# bt-snes-aa-ncp1402-attiny25-pogo.net
KiCad netlist of a schematic drawn in EAGLE
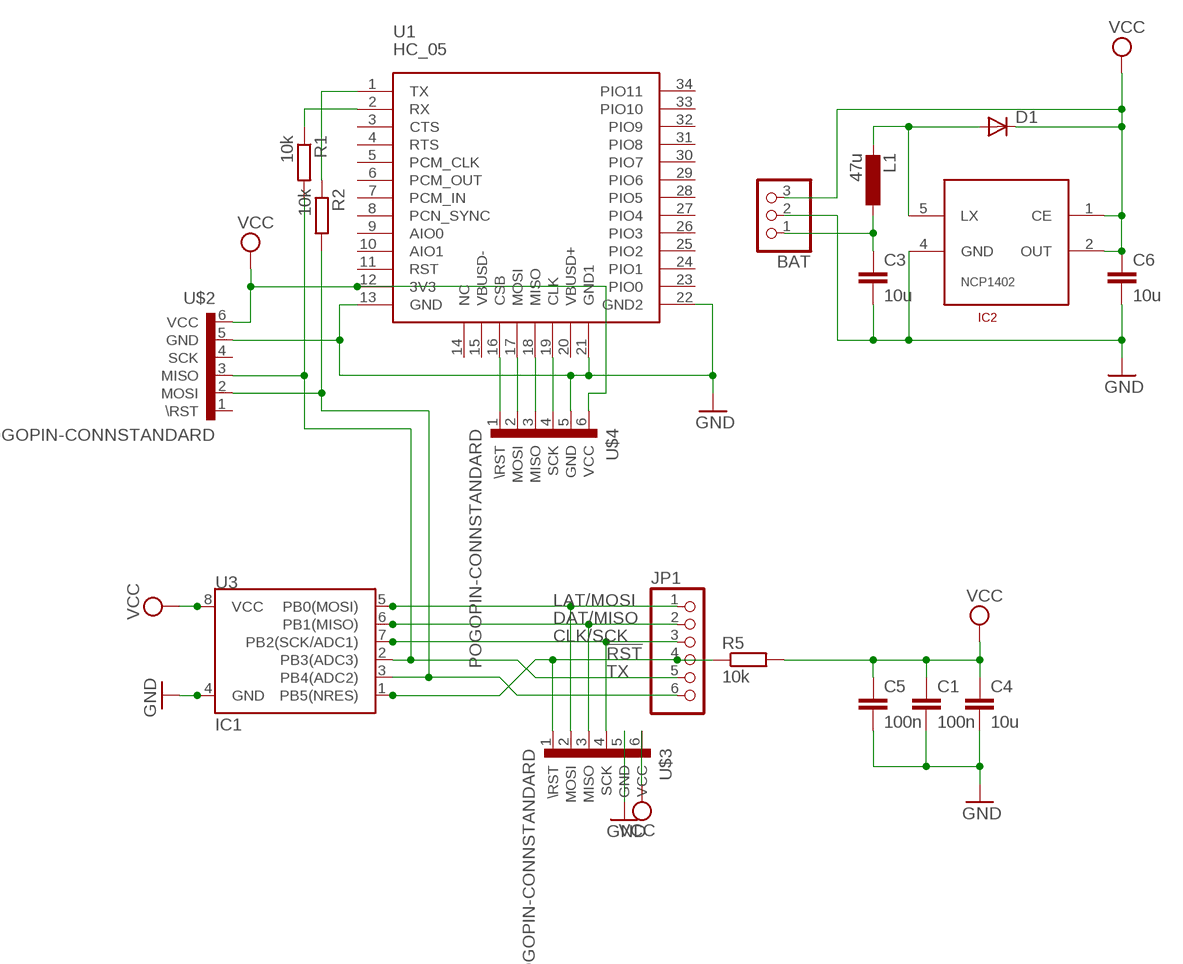
[diagram p0: schematic, sheet 1]

(export (version "E")
  (design (tool "Eeschema 10.0.6"))
  (components
    (comp (ref "BAT")
      (value "PINHD-1X3")
      (footprint "eagle-import:1X03")
      (libsource (lib "eagle-import") (part "PINHD-1X3"))
    )
    (comp (ref "C1")
      (value "100n")
      (footprint "eagle-import:C0805K")
      (libsource (lib "eagle-import") (part "C-EUC0805K"))
    )
    (comp (ref "C3")
      (value "10u")
      (footprint "eagle-import:C0805K")
      (libsource (lib "eagle-import") (part "C-EUC0805K"))
    )
    (comp (ref "C4")
      (value "10u")
      (footprint "eagle-import:C0805K")
      (libsource (lib "eagle-import") (part "C-EUC0805K"))
    )
    (comp (ref "C5")
      (value "100n")
      (footprint "eagle-import:C0805K")
      (libsource (lib "eagle-import") (part "C-EUC0805K"))
    )
    (comp (ref "C6")
      (value "10u")
      (footprint "eagle-import:C0805K")
      (libsource (lib "eagle-import") (part "C-EUC0805K"))
    )
    (comp (ref "D1")
      (value "DIODE-SOD80C")
      (footprint "eagle-import:SOD80C")
      (libsource (lib "eagle-import") (part "DIODE-SOD80C"))
    )
    (comp (ref "IC2")
      (value "NCP1402-SOT23-5")
      (footprint "eagle-import:SOT23-5")
      (libsource (lib "eagle-import") (part "NCP1402-SOT23-5"))
    )
    (comp (ref "JP1")
      (value "PINHD-1X6")
      (footprint "eagle-import:1X06")
      (libsource (lib "eagle-import") (part "PINHD-1X6"))
    )
    (comp (ref "L1")
      (value "47u")
      (footprint "eagle-import:C1210")
      (libsource (lib "eagle-import") (part "L-EUL1210"))
    )
    (comp (ref "R1")
      (value "10k")
      (footprint "eagle-import:M0805")
      (libsource (lib "eagle-import") (part "R-EU_M0805"))
    )
    (comp (ref "R2")
      (value "10k")
      (footprint "eagle-import:M0805")
      (libsource (lib "eagle-import") (part "R-EU_M0805"))
    )
    (comp (ref "R5")
      (value "10k")
      (footprint "eagle-import:M0805")
      (libsource (lib "eagle-import") (part "R-EU_M0805"))
    )
    (comp (ref "U$2")
      (value "POGOPIN-CONNSTANDARD")
      (footprint "eagle-import:POGOPROG-CONN")
      (libsource (lib "eagle-import") (part "POGOPIN-CONNSTANDARD"))
    )
    (comp (ref "U$3")
      (value "POGOPIN-CONNSTANDARD")
      (footprint "eagle-import:POGOPROG-CONN")
      (libsource (lib "eagle-import") (part "POGOPIN-CONNSTANDARD"))
    )
    (comp (ref "U$4")
      (value "POGOPIN-CONNSTANDARD")
      (footprint "eagle-import:POGOPROG-CONN")
      (libsource (lib "eagle-import") (part "POGOPIN-CONNSTANDARD"))
    )
    (comp (ref "U1")
      (value "HC_05")
      (footprint "eagle-import:BLUETOOTH_SMD")
      (libsource (lib "eagle-import") (part "HC_05"))
    )
    (comp (ref "U3")
      (value "IC1")
      (footprint "eagle-import:SO08-EIAJ")
      (libsource (lib "eagle-import") (part "ATTINY45TINY45-20-SMT"))
    )
  )
  (nets
    (net (code "1") (name "/CLK{slash}SCK") (class "Default")
      (node (ref "JP1") (pin "3") (pinfunction "3_3") (pintype "passive"))
      (node (ref "U$3") (pin "4") (pinfunction "SCK_4") (pintype "bidirectional"))
      (node (ref "U3") (pin "7") (pinfunction "PB2(SCK/ADC1)_7") (pintype "bidirectional"))
    )
    (net (code "2") (name "/DAT{slash}MISO") (class "Default")
      (node (ref "JP1") (pin "2") (pinfunction "2_2") (pintype "passive"))
      (node (ref "U$3") (pin "3") (pinfunction "MISO_3") (pintype "bidirectional"))
      (node (ref "U3") (pin "6") (pinfunction "PB1(MISO)_6") (pintype "bidirectional"))
    )
    (net (code "3") (name "/LAT{slash}MOSI") (class "Default")
      (node (ref "JP1") (pin "1") (pinfunction "1_1") (pintype "passive"))
      (node (ref "U$3") (pin "2") (pinfunction "MOSI_2") (pintype "bidirectional"))
      (node (ref "U3") (pin "5") (pinfunction "PB0(MOSI)_5") (pintype "bidirectional"))
    )
    (net (code "4") (name "/TX") (class "Default")
      (node (ref "JP1") (pin "5") (pinfunction "5_5") (pintype "passive"))
      (node (ref "R1") (pin "2") (pinfunction "2_2") (pintype "passive"))
      (node (ref "U$2") (pin "3") (pinfunction "MISO_3") (pintype "bidirectional"))
      (node (ref "U3") (pin "2") (pinfunction "PB3(ADC3)_2") (pintype "bidirectional"))
    )
    (net (code "5") (name "/~{RST}") (class "Default")
      (node (ref "JP1") (pin "4") (pinfunction "4_4") (pintype "passive"))
      (node (ref "R5") (pin "1") (pinfunction "1_1") (pintype "passive"))
      (node (ref "U$3") (pin "1") (pinfunction "\\RST_1") (pintype "bidirectional"))
      (node (ref "U3") (pin "1") (pinfunction "PB5(NRES)_1") (pintype "bidirectional"))
    )
    (net (code "6") (name "GND") (class "Default")
      (node (ref "BAT") (pin "2") (pinfunction "2_2") (pintype "passive"))
      (node (ref "C1") (pin "2") (pinfunction "2_2") (pintype "passive"))
      (node (ref "C3") (pin "2") (pinfunction "2_2") (pintype "passive"))
      (node (ref "C4") (pin "2") (pinfunction "2_2") (pintype "passive"))
      (node (ref "C5") (pin "2") (pinfunction "2_2") (pintype "passive"))
      (node (ref "C6") (pin "2") (pinfunction "2_2") (pintype "passive"))
      (node (ref "IC2") (pin "4") (pinfunction "GND_4") (pintype "bidirectional"))
      (node (ref "U$2") (pin "5") (pinfunction "GND_5") (pintype "bidirectional"))
      (node (ref "U$3") (pin "5") (pinfunction "GND_5") (pintype "bidirectional"))
      (node (ref "U$4") (pin "5") (pinfunction "GND_5") (pintype "bidirectional"))
      (node (ref "U1") (pin "13") (pinfunction "GND_13") (pintype "bidirectional"))
      (node (ref "U1") (pin "21") (pinfunction "GND1_21") (pintype "bidirectional"))
      (node (ref "U1") (pin "22") (pinfunction "GND2_22") (pintype "bidirectional"))
      (node (ref "U3") (pin "4") (pinfunction "GND_4") (pintype "bidirectional"))
    )
    (net (code "7") (name "Net-(BAT-Pad1)") (class "Default")
      (node (ref "BAT") (pin "1") (pinfunction "1_1") (pintype "passive"))
      (node (ref "C3") (pin "1") (pinfunction "1_1") (pintype "passive"))
      (node (ref "L1") (pin "1") (pinfunction "1_1") (pintype "passive"))
    )
    (net (code "8") (name "Net-(IC2-LX)") (class "Default")
      (node (ref "D1") (pin "A") (pinfunction "A_A") (pintype "passive"))
      (node (ref "IC2") (pin "5") (pinfunction "LX_5") (pintype "bidirectional"))
      (node (ref "L1") (pin "2") (pinfunction "2_2") (pintype "passive"))
    )
    (net (code "9") (name "Net-(U$2-MOSI)") (class "Default")
      (node (ref "JP1") (pin "6") (pinfunction "6_6") (pintype "passive"))
      (node (ref "R2") (pin "2") (pinfunction "2_2") (pintype "passive"))
      (node (ref "U$2") (pin "2") (pinfunction "MOSI_2") (pintype "bidirectional"))
      (node (ref "U3") (pin "3") (pinfunction "PB4(ADC2)_3") (pintype "bidirectional"))
    )
    (net (code "10") (name "Net-(U$4-MISO)") (class "Default")
      (node (ref "U$4") (pin "3") (pinfunction "MISO_3") (pintype "bidirectional"))
      (node (ref "U1") (pin "18") (pinfunction "MISO_18") (pintype "bidirectional"))
    )
    (net (code "11") (name "Net-(U$4-MOSI)") (class "Default")
      (node (ref "U$4") (pin "2") (pinfunction "MOSI_2") (pintype "bidirectional"))
      (node (ref "U1") (pin "17") (pinfunction "MOSI_17") (pintype "bidirectional"))
    )
    (net (code "12") (name "Net-(U$4-SCK)") (class "Default")
      (node (ref "U$4") (pin "4") (pinfunction "SCK_4") (pintype "bidirectional"))
      (node (ref "U1") (pin "19") (pinfunction "CLK_19") (pintype "bidirectional"))
    )
    (net (code "13") (name "Net-(U$4-\\RST)") (class "Default")
      (node (ref "U$4") (pin "1") (pinfunction "\\RST_1") (pintype "bidirectional"))
      (node (ref "U1") (pin "16") (pinfunction "CSB_16") (pintype "bidirectional"))
    )
    (net (code "14") (name "Net-(U1-RX)") (class "Default")
      (node (ref "R1") (pin "1") (pinfunction "1_1") (pintype "passive"))
      (node (ref "U1") (pin "2") (pinfunction "RX_2") (pintype "bidirectional"))
    )
    (net (code "15") (name "Net-(U1-TX)") (class "Default")
      (node (ref "R2") (pin "1") (pinfunction "1_1") (pintype "passive"))
      (node (ref "U1") (pin "1") (pinfunction "TX_1") (pintype "bidirectional"))
    )
    (net (code "16") (name "VCC") (class "Default")
      (node (ref "BAT") (pin "3") (pinfunction "3_3") (pintype "passive"))
      (node (ref "C1") (pin "1") (pinfunction "1_1") (pintype "passive"))
      (node (ref "C4") (pin "1") (pinfunction "1_1") (pintype "passive"))
      (node (ref "C5") (pin "1") (pinfunction "1_1") (pintype "passive"))
      (node (ref "C6") (pin "1") (pinfunction "1_1") (pintype "passive"))
      (node (ref "D1") (pin "C") (pinfunction "C_C") (pintype "passive"))
      (node (ref "IC2") (pin "1") (pinfunction "CE_1") (pintype "bidirectional"))
      (node (ref "IC2") (pin "2") (pinfunction "OUT_2") (pintype "bidirectional"))
      (node (ref "R5") (pin "2") (pinfunction "2_2") (pintype "passive"))
      (node (ref "U$2") (pin "6") (pinfunction "VCC_6") (pintype "bidirectional"))
      (node (ref "U$3") (pin "6") (pinfunction "VCC_6") (pintype "bidirectional"))
      (node (ref "U$4") (pin "6") (pinfunction "VCC_6") (pintype "bidirectional"))
      (node (ref "U1") (pin "12") (pinfunction "3V3_12") (pintype "bidirectional"))
      (node (ref "U3") (pin "8") (pinfunction "VCC_8") (pintype "bidirectional"))
    )
    (net (code "17") (name "unconnected-(U$2-SCK-Pad4)") (class "Default")
      (node (ref "U$2") (pin "4") (pinfunction "SCK_4") (pintype "bidirectional"))
    )
    (net (code "18") (name "unconnected-(U$2-\\RST-Pad1)") (class "Default")
      (node (ref "U$2") (pin "1") (pinfunction "\\RST_1") (pintype "bidirectional"))
    )
    (net (code "19") (name "unconnected-(U1-AIO0-Pad9)") (class "Default")
      (node (ref "U1") (pin "9") (pinfunction "AIO0_9") (pintype "bidirectional"))
    )
    (net (code "20") (name "unconnected-(U1-AIO1-Pad10)") (class "Default")
      (node (ref "U1") (pin "10") (pinfunction "AIO1_10") (pintype "bidirectional"))
    )
    (net (code "21") (name "unconnected-(U1-CTS-Pad3)") (class "Default")
      (node (ref "U1") (pin "3") (pinfunction "CTS_3") (pintype "bidirectional"))
    )
    (net (code "22") (name "unconnected-(U1-NC-Pad14)") (class "Default")
      (node (ref "U1") (pin "14") (pinfunction "NC_14") (pintype "bidirectional"))
    )
    (net (code "23") (name "unconnected-(U1-PCM_CLK-Pad5)") (class "Default")
      (node (ref "U1") (pin "5") (pinfunction "PCM_CLK_5") (pintype "bidirectional"))
    )
    (net (code "24") (name "unconnected-(U1-PCM_IN-Pad7)") (class "Default")
      (node (ref "U1") (pin "7") (pinfunction "PCM_IN_7") (pintype "bidirectional"))
    )
    (net (code "25") (name "unconnected-(U1-PCM_OUT-Pad6)") (class "Default")
      (node (ref "U1") (pin "6") (pinfunction "PCM_OUT_6") (pintype "bidirectional"))
    )
    (net (code "26") (name "unconnected-(U1-PCN_SYNC-Pad8)") (class "Default")
      (node (ref "U1") (pin "8") (pinfunction "PCN_SYNC_8") (pintype "bidirectional"))
    )
    (net (code "27") (name "unconnected-(U1-PIO0-Pad23)") (class "Default")
      (node (ref "U1") (pin "23") (pinfunction "PIO0_23") (pintype "bidirectional"))
    )
    (net (code "28") (name "unconnected-(U1-PIO1-Pad24)") (class "Default")
      (node (ref "U1") (pin "24") (pinfunction "PIO1_24") (pintype "bidirectional"))
    )
    (net (code "29") (name "unconnected-(U1-PIO2-Pad25)") (class "Default")
      (node (ref "U1") (pin "25") (pinfunction "PIO2_25") (pintype "bidirectional"))
    )
    (net (code "30") (name "unconnected-(U1-PIO3-Pad26)") (class "Default")
      (node (ref "U1") (pin "26") (pinfunction "PIO3_26") (pintype "bidirectional"))
    )
    (net (code "31") (name "unconnected-(U1-PIO4-Pad27)") (class "Default")
      (node (ref "U1") (pin "27") (pinfunction "PIO4_27") (pintype "bidirectional"))
    )
    (net (code "32") (name "unconnected-(U1-PIO5-Pad28)") (class "Default")
      (node (ref "U1") (pin "28") (pinfunction "PIO5_28") (pintype "bidirectional"))
    )
    (net (code "33") (name "unconnected-(U1-PIO6-Pad29)") (class "Default")
      (node (ref "U1") (pin "29") (pinfunction "PIO6_29") (pintype "bidirectional"))
    )
    (net (code "34") (name "unconnected-(U1-PIO7-Pad30)") (class "Default")
      (node (ref "U1") (pin "30") (pinfunction "PIO7_30") (pintype "bidirectional"))
    )
    (net (code "35") (name "unconnected-(U1-PIO8-Pad31)") (class "Default")
      (node (ref "U1") (pin "31") (pinfunction "PIO8_31") (pintype "bidirectional"))
    )
    (net (code "36") (name "unconnected-(U1-PIO9-Pad32)") (class "Default")
      (node (ref "U1") (pin "32") (pinfunction "PIO9_32") (pintype "bidirectional"))
    )
    (net (code "37") (name "unconnected-(U1-PIO10-Pad33)") (class "Default")
      (node (ref "U1") (pin "33") (pinfunction "PIO10_33") (pintype "bidirectional"))
    )
    (net (code "38") (name "unconnected-(U1-PIO11-Pad34)") (class "Default")
      (node (ref "U1") (pin "34") (pinfunction "PIO11_34") (pintype "bidirectional"))
    )
    (net (code "39") (name "unconnected-(U1-RST-Pad11)") (class "Default")
      (node (ref "U1") (pin "11") (pinfunction "RST_11") (pintype "bidirectional"))
    )
    (net (code "40") (name "unconnected-(U1-RTS-Pad4)") (class "Default")
      (node (ref "U1") (pin "4") (pinfunction "RTS_4") (pintype "bidirectional"))
    )
    (net (code "41") (name "unconnected-(U1-VBUSD+-Pad20)") (class "Default")
      (node (ref "U1") (pin "20") (pinfunction "VBUSD+_20") (pintype "bidirectional"))
    )
    (net (code "42") (name "unconnected-(U1-VBUSD--Pad15)") (class "Default")
      (node (ref "U1") (pin "15") (pinfunction "VBUSD-_15") (pintype "bidirectional"))
    )
  )
)
